# 1-Schematic_Vitulus-connector_main_unit.net
KiCad netlist of a schematic drawn in EasyEDA
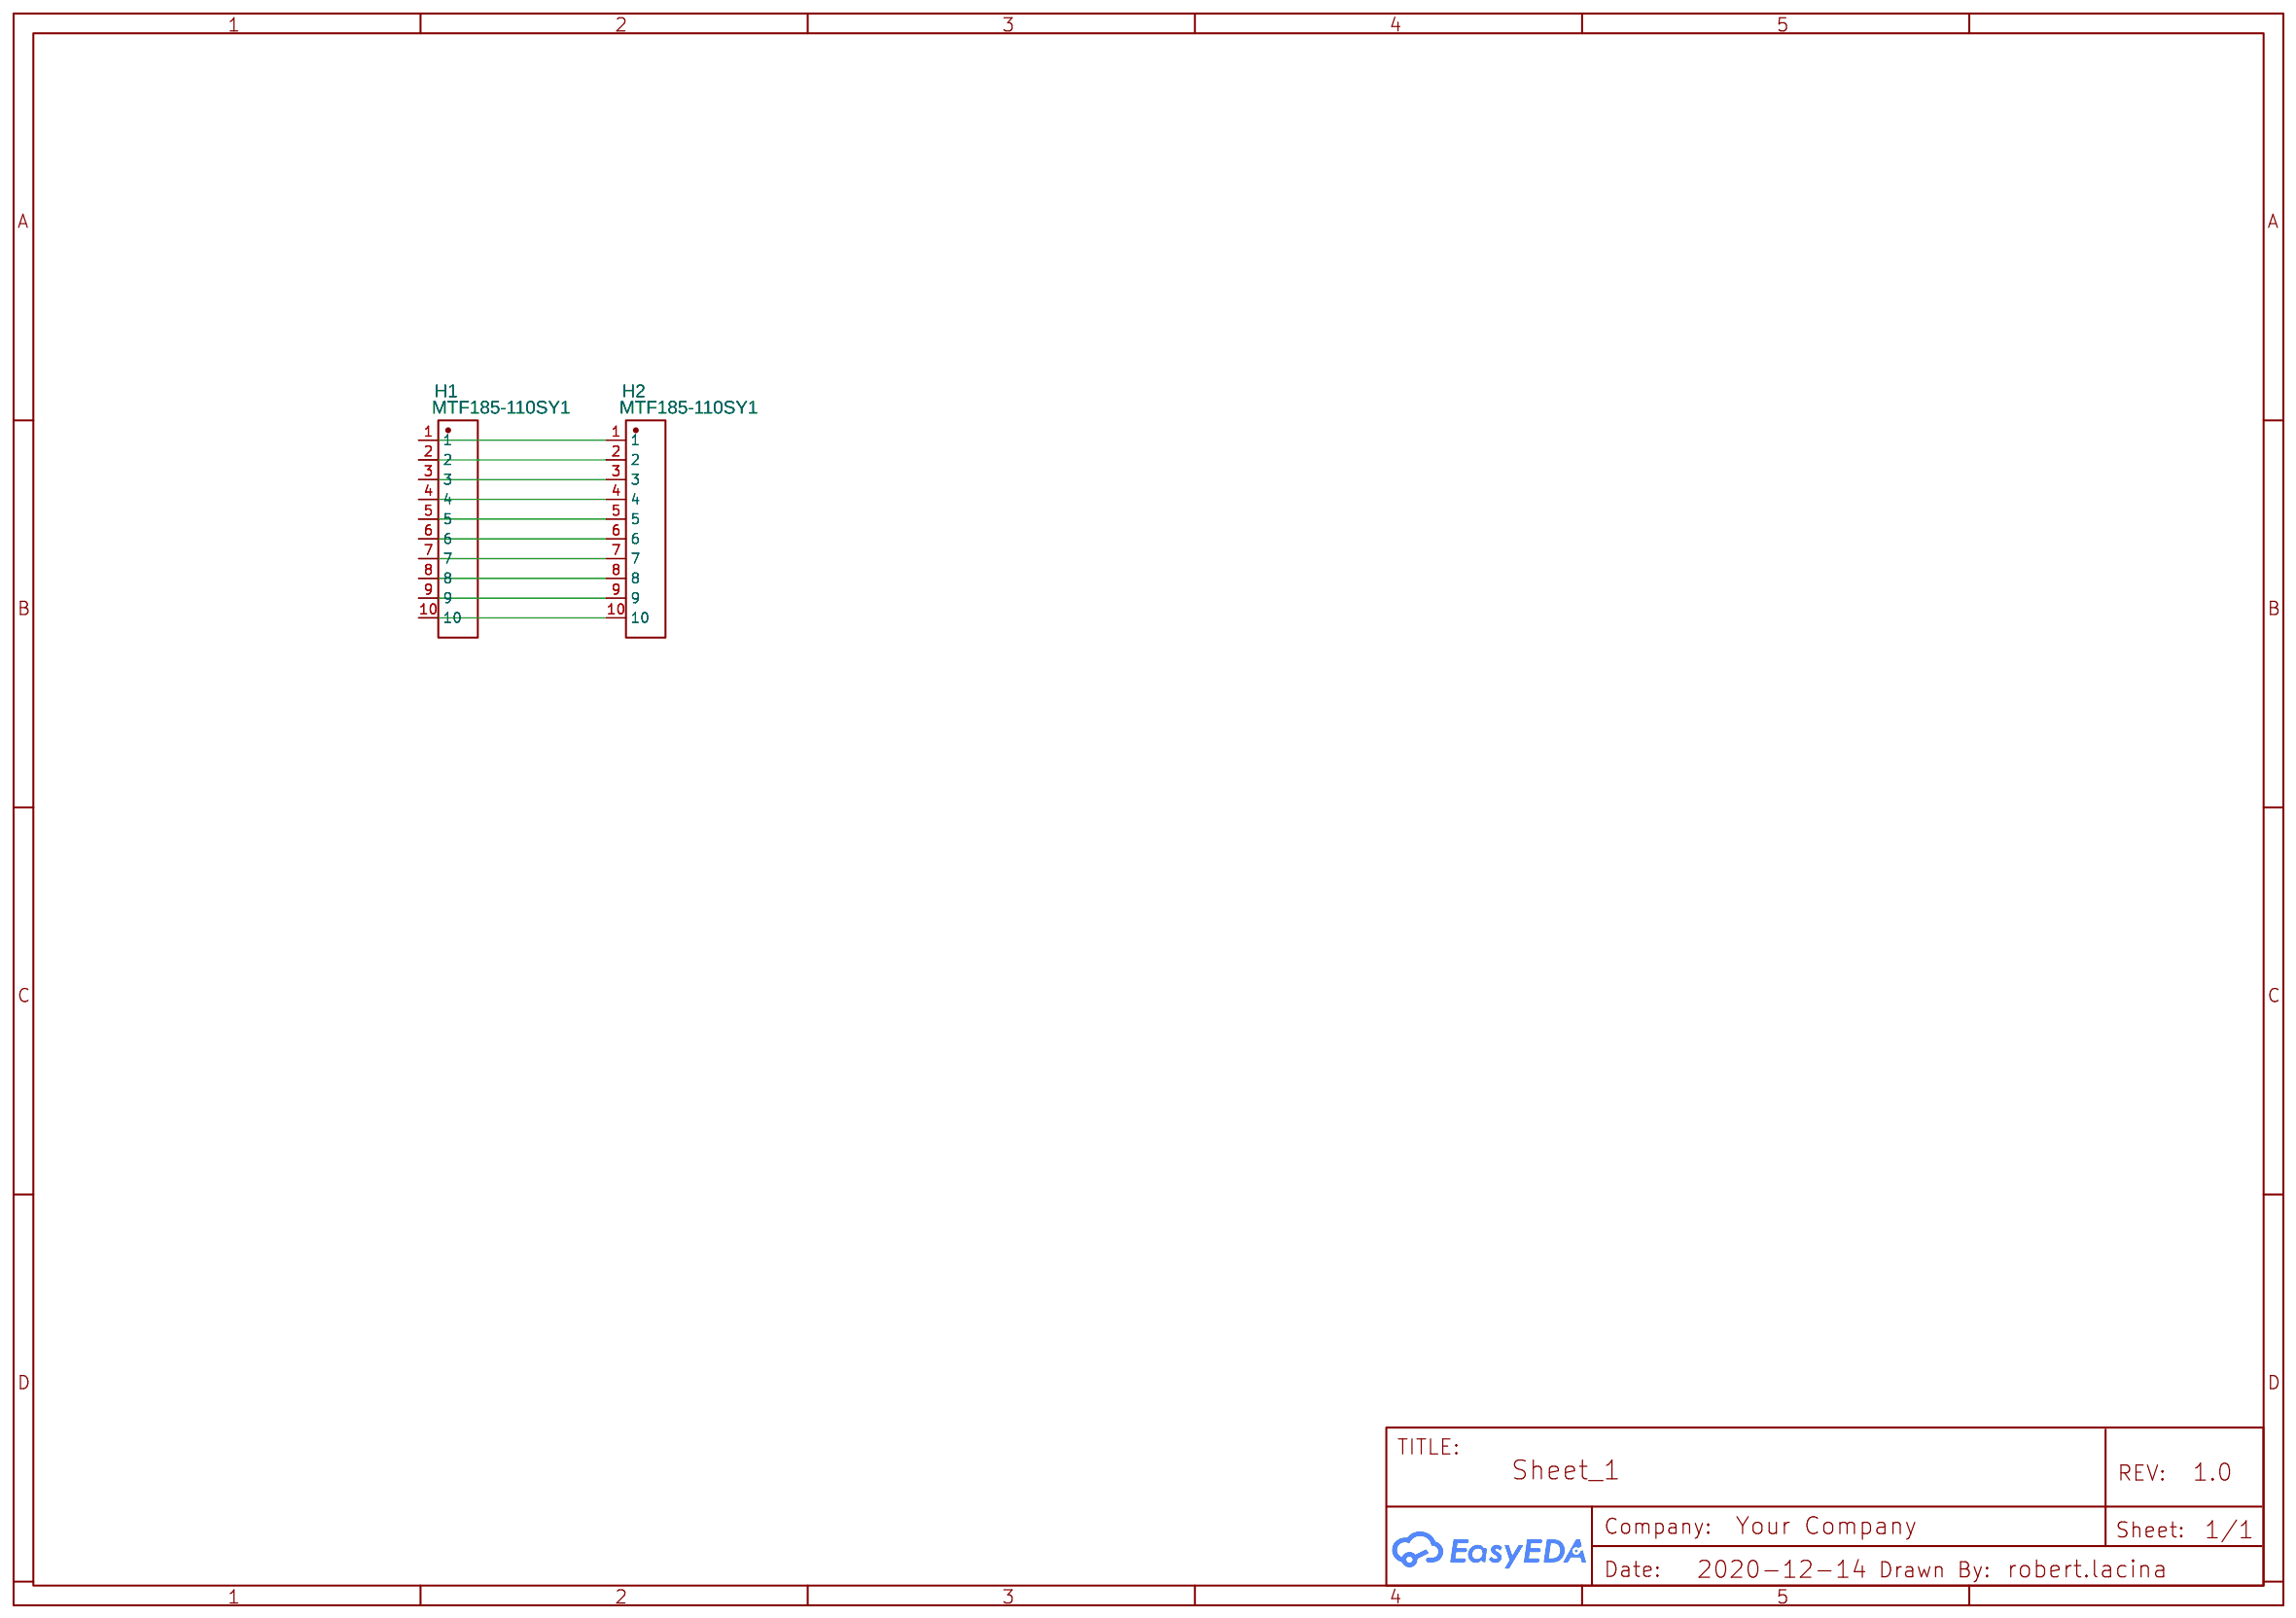
[diagram p0: schematic sheet]

(export (version "E")
  (design (tool "Eeschema 10.0.6"))
  (components
    (comp (ref "H1")
      (value "MTF185-110SY1")
      (fields (field (name "BOM_Supplier Part") "C358723"))
      (libsource (lib "") (part "MTF185-110SY1"))
    )
    (comp (ref "H2")
      (value "MTF185-110SY1")
      (fields (field (name "BOM_Supplier Part") "C358723"))
      (libsource (lib "") (part "MTF185-110SY1"))
    )
  )
  (nets
    (net (code "1") (name "Net-(H1-Pad1)") (class "Default")
      (node (ref "H1") (pin "1") (pinfunction "1_1") (pintype "unspecified"))
      (node (ref "H2") (pin "1") (pinfunction "1_1") (pintype "unspecified"))
    )
    (net (code "2") (name "Net-(H1-Pad2)") (class "Default")
      (node (ref "H1") (pin "2") (pinfunction "2_2") (pintype "unspecified"))
      (node (ref "H2") (pin "2") (pinfunction "2_2") (pintype "unspecified"))
    )
    (net (code "3") (name "Net-(H1-Pad3)") (class "Default")
      (node (ref "H1") (pin "3") (pinfunction "3_3") (pintype "unspecified"))
      (node (ref "H2") (pin "3") (pinfunction "3_3") (pintype "unspecified"))
    )
    (net (code "4") (name "Net-(H1-Pad4)") (class "Default")
      (node (ref "H1") (pin "4") (pinfunction "4_4") (pintype "unspecified"))
      (node (ref "H2") (pin "4") (pinfunction "4_4") (pintype "unspecified"))
    )
    (net (code "5") (name "Net-(H1-Pad5)") (class "Default")
      (node (ref "H1") (pin "5") (pinfunction "5_5") (pintype "unspecified"))
      (node (ref "H2") (pin "5") (pinfunction "5_5") (pintype "unspecified"))
    )
    (net (code "6") (name "Net-(H1-Pad6)") (class "Default")
      (node (ref "H1") (pin "6") (pinfunction "6_6") (pintype "unspecified"))
      (node (ref "H2") (pin "6") (pinfunction "6_6") (pintype "unspecified"))
    )
    (net (code "7") (name "Net-(H1-Pad7)") (class "Default")
      (node (ref "H1") (pin "7") (pinfunction "7_7") (pintype "unspecified"))
      (node (ref "H2") (pin "7") (pinfunction "7_7") (pintype "unspecified"))
    )
    (net (code "8") (name "Net-(H1-Pad8)") (class "Default")
      (node (ref "H1") (pin "8") (pinfunction "8_8") (pintype "unspecified"))
      (node (ref "H2") (pin "8") (pinfunction "8_8") (pintype "unspecified"))
    )
    (net (code "9") (name "Net-(H1-Pad9)") (class "Default")
      (node (ref "H1") (pin "9") (pinfunction "9_9") (pintype "unspecified"))
      (node (ref "H2") (pin "9") (pinfunction "9_9") (pintype "unspecified"))
    )
    (net (code "10") (name "Net-(H1-Pad10)") (class "Default")
      (node (ref "H1") (pin "10") (pinfunction "10_10") (pintype "unspecified"))
      (node (ref "H2") (pin "10") (pinfunction "10_10") (pintype "unspecified"))
    )
  )
)
